# TXpreamp.net
KiCad netlist of a schematic drawn in Altium Designer
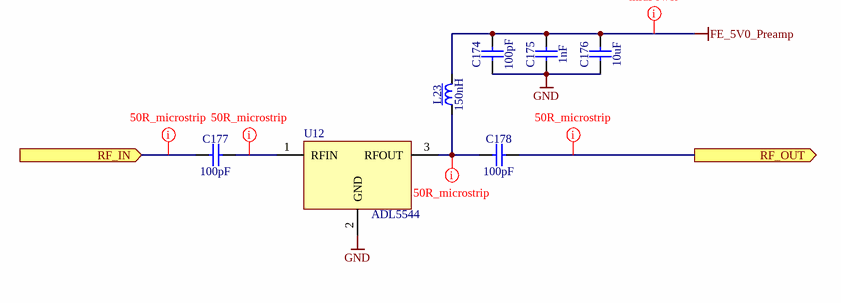
[diagram p0: TXpreamp.SchDoc]

(export (version "E")
  (design (tool "Eeschema 10.0.6"))
  (components
    (comp (ref "C174")
      (value "100pF")
      (footprint "CAPC1005X55N")
      (description "Non-polarised capacitor")
      (fields
        (field (name "PART NUMBER") "CC0402_100PF_50V_5%_C0G")
        (field (name "VOLTAGE") "50V")
        (field (name "AUTHOR") "CERN DEM JLC")
      )
      (libsource (lib "Capacitors") (part "Capacitor - non polarized"))
    )
    (comp (ref "C175")
      (value "1nF")
      (footprint "CAPC1005X55N")
      (description "Non-polarised capacitor")
      (fields
        (field (name "PART NUMBER") "CC0402_1NF_50V_10%_X7R")
        (field (name "VOLTAGE") "50V")
        (field (name "AUTHOR") "CERN DEM JLC")
      )
      (libsource (lib "Capacitors") (part "Capacitor - non polarized"))
    )
    (comp (ref "C176")
      (value "10uF")
      (footprint "CAPC3216X180N")
      (description "Non-polarised capacitor")
      (fields
        (field (name "PART NUMBER") "CC1206_10UF_25V_10%_X7R")
        (field (name "VOLTAGE") "25V")
        (field (name "AUTHOR") "CERN DEM JLC")
      )
      (libsource (lib "Capacitors") (part "Capacitor - non polarized"))
    )
    (comp (ref "C177")
      (value "100pF")
      (footprint "CAPC1005X55N")
      (description "Non-polarised capacitor")
      (fields
        (field (name "PART NUMBER") "CC0402_100PF_50V_5%_C0G")
        (field (name "VOLTAGE") "50V")
        (field (name "AUTHOR") "CERN DEM JLC")
      )
      (libsource (lib "Capacitors") (part "Capacitor - non polarized"))
    )
    (comp (ref "C178")
      (value "100pF")
      (footprint "CAPC1005X55N")
      (description "Non-polarised capacitor")
      (fields
        (field (name "PART NUMBER") "CC0402_100PF_50V_5%_C0G")
        (field (name "VOLTAGE") "50V")
        (field (name "AUTHOR") "CERN DEM JLC")
      )
      (libsource (lib "Capacitors") (part "Capacitor - non polarized"))
    )
    (comp (ref "L23")
      (value "150nH")
      (footprint "IND_COILCRAFT_0805CS")
      (description "Inductor With Core")
      (fields
        (field (name "PART NUMBER") "IND_150NH_2%_COILCRAFT_0805CS")
        (field (name "POWER") "400mA")
        (field (name "AUTHOR") "CERN DEM JLC")
      )
      (libsource (lib "Inductors & Transformers") (part "Inductor With Magnetic core"))
    )
    (comp (ref "U12") (value "ADL5544") (footprint "ADL5544") (libsource (lib "FMC_SDR") (part "ADL5544")))
  )
  (nets
    (net (code "1") (name "/RF_IN") (class "Default")
      (node (ref "C177") (pin "1") (pinfunction "1_1") (pintype "passive"))
    )
    (net (code "2") (name "/RF_OUT") (class "Default")
      (node (ref "C178") (pin "2") (pinfunction "2_2") (pintype "passive"))
    )
    (net (code "3") (name "FE_5V0_Preamp") (class "Default")
      (node (ref "C174") (pin "2") (pinfunction "2_2") (pintype "passive"))
      (node (ref "C175") (pin "2") (pinfunction "2_2") (pintype "passive"))
      (node (ref "C176") (pin "2") (pinfunction "2_2") (pintype "passive"))
      (node (ref "L23") (pin "2") (pinfunction "2_2") (pintype "passive"))
    )
    (net (code "4") (name "GND") (class "Default")
      (node (ref "C174") (pin "1") (pinfunction "1_1") (pintype "passive"))
      (node (ref "C175") (pin "1") (pinfunction "1_1") (pintype "passive"))
      (node (ref "C176") (pin "1") (pinfunction "1_1") (pintype "passive"))
      (node (ref "U12") (pin "2") (pinfunction "GND_2") (pintype "passive"))
    )
    (net (code "5") (name "Net-(U12-RFIN)") (class "Default")
      (node (ref "C177") (pin "2") (pinfunction "2_2") (pintype "passive"))
      (node (ref "U12") (pin "1") (pinfunction "RFIN_1") (pintype "passive"))
    )
    (net (code "6") (name "Net-(U12-RFOUT)") (class "Default")
      (node (ref "C178") (pin "1") (pinfunction "1_1") (pintype "passive"))
      (node (ref "L23") (pin "1") (pinfunction "1_1") (pintype "passive"))
      (node (ref "U12") (pin "3") (pinfunction "RFOUT_3") (pintype "passive"))
    )
  )
)
